# X-LINK-A_V2_0.net
KiCad netlist of a schematic drawn in Altium Designer
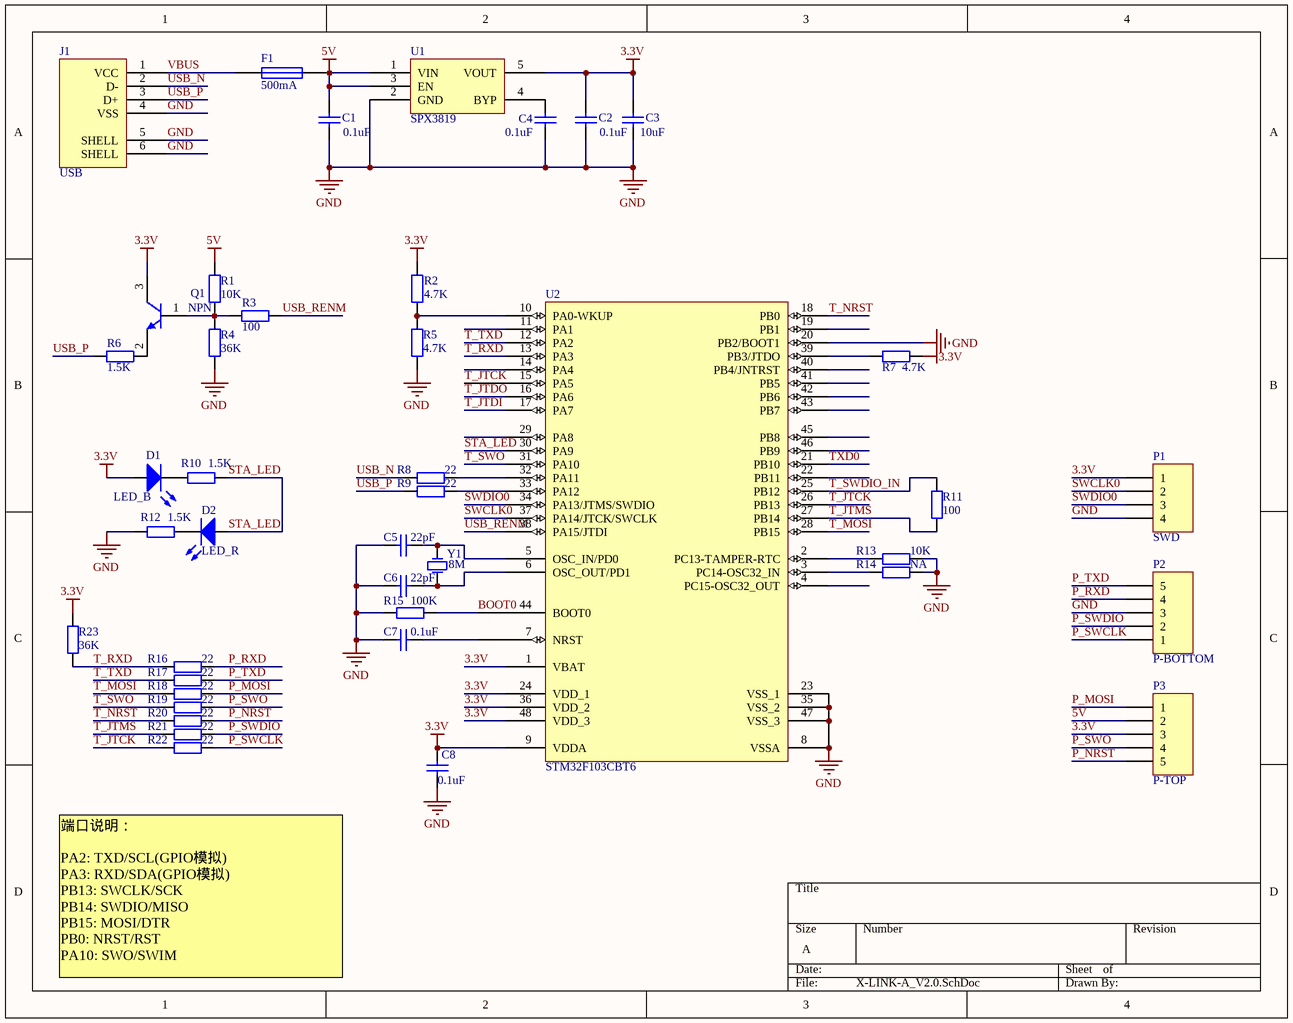
[diagram p0: X-LINK-A_V2.0.SchDoc]

(export (version "E")
  (design (tool "Eeschema 10.0.6"))
  (components
    (comp (ref "C1")
      (value "0.1uF")
      (footprint "C-0603")
      (description "Capacitor")
      (fields (field (name "Comment") "Cap") (field (name "PUBLISHER") "Altium Limited"))
      (libsource (lib "Miscellaneous Devices") (part "Cap"))
    )
    (comp (ref "C2")
      (value "0.1uF")
      (footprint "C-0603")
      (description "Capacitor")
      (fields (field (name "Comment") "Cap") (field (name "PUBLISHER") "Altium Limited"))
      (libsource (lib "Miscellaneous Devices") (part "Cap"))
    )
    (comp (ref "C3")
      (value "10uF")
      (footprint "C-0603")
      (description "Capacitor")
      (fields (field (name "Comment") "Cap") (field (name "PUBLISHER") "Altium Limited"))
      (libsource (lib "Miscellaneous Devices") (part "Cap"))
    )
    (comp (ref "C4")
      (value "0.1uF")
      (footprint "C-0603")
      (description "Capacitor")
      (fields (field (name "Comment") "Cap") (field (name "PUBLISHER") "Altium Limited"))
      (libsource (lib "Miscellaneous Devices") (part "Cap"))
    )
    (comp (ref "C5")
      (value "22pF")
      (footprint "C-0603")
      (fields (field (name "Comment") "Cap"))
      (libsource (lib "WK_PCB") (part "Cap"))
    )
    (comp (ref "C6")
      (value "22pF")
      (footprint "C-0603")
      (fields (field (name "Comment") "Cap"))
      (libsource (lib "WK_PCB") (part "Cap"))
    )
    (comp (ref "C7")
      (value "0.1uF")
      (footprint "C-0603")
      (fields (field (name "Comment") "Cap"))
      (libsource (lib "WK_PCB") (part "Cap"))
    )
    (comp (ref "C8")
      (value "0.1uF")
      (footprint "C-0603")
      (description "Capacitor")
      (fields (field (name "Comment") "Cap") (field (name "PUBLISHER") "Altium Limited"))
      (libsource (lib "Miscellaneous Devices") (part "Cap"))
    )
    (comp (ref "D1")
      (value "LED_B")
      (footprint "SMT_LED_0603")
      (description "Typical RED, GREEN, YELLOW, AMBER GaAs LED")
      (fields (field (name "PUBLISHER") "Altium Limited"))
      (libsource (lib "ST-Link-V2.2") (part "LED2"))
    )
    (comp (ref "D2")
      (value "LED_R")
      (footprint "SMT_LED_0603")
      (description "Typical RED, GREEN, YELLOW, AMBER GaAs LED")
      (fields (field (name "PUBLISHER") "Altium Limited"))
      (libsource (lib "ST-Link-V2.2") (part "LED2"))
    )
    (comp (ref "F1")
      (value "500mA")
      (footprint "0805-1")
      (description "保险丝")
      (fields (field (name "Comment") "Fuse1"))
      (libsource (lib "ST-Link-V2.2") (part "Fuse1"))
    )
    (comp (ref "J1")
      (value "USB")
      (footprint "USB-B")
      (description "USB接口")
      (libsource (lib "HDR_Fszhang") (part "USB"))
    )
    (comp (ref "P1")
      (value "SWD")
      (footprint "SIP4-1.27")
      (description "Header, 4-Pin")
      (fields (field (name "PUBLISHER") "Altium Limited"))
      (libsource (lib "Miscellaneous Connectors") (part "Header 4"))
    )
    (comp (ref "P2")
      (value "P-BOTTOM")
      (footprint "HEADER_5")
      (description "Header, 5-Pin")
      (fields (field (name "PUBLISHER") "Altium Limited"))
      (libsource (lib "") (part "Header 5_1"))
    )
    (comp (ref "P3")
      (value "P-TOP")
      (footprint "HEADER_5")
      (description "Header, 5-Pin")
      (fields (field (name "PUBLISHER") "Altium Limited"))
      (libsource (lib "Miscellaneous Connectors") (part "Header 5"))
    )
    (comp (ref "Q1")
      (value "NPN")
      (footprint "SOT23-3")
      (description "贴片三极管")
      (fields (field (name "PUBLISHER") "Altium Limited"))
      (libsource (lib "Fszhang") (part "NPN1"))
    )
    (comp (ref "R1")
      (value "10K")
      (footprint "0603-1")
      (description "贴片电阻")
      (fields (field (name "Comment") "Res1") (field (name "PUBLISHER") "Altium Limited"))
      (libsource (lib "") (part "Res1_1"))
    )
    (comp (ref "R2")
      (value "4.7K")
      (footprint "0603-1")
      (description "Resistor")
      (fields (field (name "Comment") "Res2") (field (name "PUBLISHER") "Altium Limited"))
      (libsource (lib "Miscellaneous Devices") (part "Res2"))
    )
    (comp (ref "R3")
      (value "100")
      (footprint "0603-1")
      (description "贴片电阻")
      (fields (field (name "Comment") "Res1") (field (name "PUBLISHER") "Altium Limited"))
      (libsource (lib "") (part "Res1_2"))
    )
    (comp (ref "R4")
      (value "36K")
      (footprint "0603-1")
      (description "贴片电阻")
      (fields (field (name "Comment") "Res1") (field (name "PUBLISHER") "Altium Limited"))
      (libsource (lib "") (part "Res1_1"))
    )
    (comp (ref "R5")
      (value "4.7K")
      (footprint "0603-1")
      (description "Resistor")
      (fields (field (name "Comment") "Res2") (field (name "PUBLISHER") "Altium Limited"))
      (libsource (lib "Miscellaneous Devices") (part "Res2"))
    )
    (comp (ref "R6")
      (value "1.5K")
      (footprint "0603-1")
      (description "贴片电阻")
      (fields (field (name "Comment") "Res1") (field (name "PUBLISHER") "Altium Limited"))
      (libsource (lib "Fszhang") (part "Res1"))
    )
    (comp (ref "R7")
      (value "4.7K")
      (footprint "0603-1")
      (description "Resistor")
      (fields (field (name "Comment") "Res2") (field (name "PUBLISHER") "Altium Limited"))
      (libsource (lib "") (part "Res2_1"))
    )
    (comp (ref "R8")
      (value "22")
      (footprint "0603-1")
      (description "Resistor")
      (fields (field (name "Comment") "Res2") (field (name "PUBLISHER") "Altium Limited"))
      (libsource (lib "") (part "Res2_1"))
    )
    (comp (ref "R9")
      (value "22")
      (footprint "0603-1")
      (description "Resistor")
      (fields (field (name "Comment") "Res2") (field (name "PUBLISHER") "Altium Limited"))
      (libsource (lib "") (part "Res2_1"))
    )
    (comp (ref "R10")
      (value "1.5K")
      (footprint "0603-1")
      (description "Resistor")
      (fields (field (name "Comment") "Res2") (field (name "PUBLISHER") "Altium Limited"))
      (libsource (lib "") (part "Res2_1"))
    )
    (comp (ref "R11")
      (value "100")
      (footprint "0603-1")
      (description "Resistor")
      (fields (field (name "Comment") "Res2") (field (name "PUBLISHER") "Altium Limited"))
      (libsource (lib "Miscellaneous Devices") (part "Res2"))
    )
    (comp (ref "R12")
      (value "1.5K")
      (footprint "0603-1")
      (description "Resistor")
      (fields (field (name "Comment") "Res2") (field (name "PUBLISHER") "Altium Limited"))
      (libsource (lib "Miscellaneous Devices") (part "Res2"))
    )
    (comp (ref "R13")
      (value "10K")
      (footprint "0603-1")
      (description "贴片电阻")
      (fields (field (name "Comment") "Res1") (field (name "PUBLISHER") "Altium Limited"))
      (libsource (lib "") (part "Res1_2"))
    )
    (comp (ref "R14")
      (value "NA")
      (footprint "0603-1")
      (description "贴片电阻")
      (fields (field (name "Comment") "Res1") (field (name "PUBLISHER") "Altium Limited"))
      (libsource (lib "") (part "Res1_2"))
    )
    (comp (ref "R15")
      (value "100K")
      (footprint "0603-1")
      (description "Resistor")
      (fields (field (name "Comment") "Res2") (field (name "PUBLISHER") "Altium Limited"))
      (libsource (lib "") (part "Res2_1"))
    )
    (comp (ref "R16")
      (value "22")
      (footprint "0603-1")
      (description "Resistor")
      (fields (field (name "Comment") "Res2") (field (name "PUBLISHER") "Altium Limited"))
      (libsource (lib "") (part "Res2_1"))
    )
    (comp (ref "R17")
      (value "22")
      (footprint "0603-1")
      (description "Resistor")
      (fields (field (name "Comment") "Res2") (field (name "PUBLISHER") "Altium Limited"))
      (libsource (lib "") (part "Res2_1"))
    )
    (comp (ref "R18")
      (value "22")
      (footprint "0603-1")
      (description "Resistor")
      (fields (field (name "Comment") "Res2") (field (name "PUBLISHER") "Altium Limited"))
      (libsource (lib "") (part "Res2_1"))
    )
    (comp (ref "R19")
      (value "22")
      (footprint "0603-1")
      (description "Resistor")
      (fields (field (name "Comment") "Res2") (field (name "PUBLISHER") "Altium Limited"))
      (libsource (lib "") (part "Res2_1"))
    )
    (comp (ref "R20")
      (value "22")
      (footprint "0603-1")
      (description "Resistor")
      (fields (field (name "Comment") "Res2") (field (name "PUBLISHER") "Altium Limited"))
      (libsource (lib "") (part "Res2_1"))
    )
    (comp (ref "R21")
      (value "22")
      (footprint "0603-1")
      (description "Resistor")
      (fields (field (name "Comment") "Res2") (field (name "PUBLISHER") "Altium Limited"))
      (libsource (lib "") (part "Res2_1"))
    )
    (comp (ref "R22")
      (value "22")
      (footprint "0603-1")
      (description "Resistor")
      (fields (field (name "Comment") "Res2") (field (name "PUBLISHER") "Altium Limited"))
      (libsource (lib "") (part "Res2_1"))
    )
    (comp (ref "R23")
      (value "36K")
      (footprint "0603-1")
      (description "贴片电阻")
      (fields (field (name "Comment") "Res1") (field (name "PUBLISHER") "Altium Limited"))
      (libsource (lib "") (part "Res1_1"))
    )
    (comp (ref "U1") (value "SPX3819") (footprint "SOT23-5") (libsource (lib "Schlib1") (part "SPX3819")))
    (comp (ref "U2")
      (value "STM32F103CBT6")
      (footprint "LQFP48_N")
      (description "STM32 ARM-based 32-bit MCU with 64 Kbytes Flash, 48-pin LQFP, Industrial Temperature")
      (fields (field (name "PUBLISHER") "Altium Limited"))
      (libsource (lib "ST Microcontroller 32-Bit STM32") (part "STM32F103C8T6"))
    )
    (comp (ref "Y1")
      (value "8M")
      (footprint "XAL5032 2-Leads")
      (description "Crystal Oscillator")
      (fields
        (field (name "MANUFACTURER") "Generic Components")
        (field (name "PUBLISHER") "Altium Hobart Technology Centre")
      )
      (libsource (lib "*") (part "XTAL"))
    )
  )
  (nets
    (net (code "1") (name "/BOOT0") (class "Default")
      (node (ref "R15") (pin "2") (pinfunction "2_2") (pintype "passive"))
      (node (ref "U2") (pin "44") (pinfunction "BOOT0_44") (pintype "passive"))
    )
    (net (code "2") (name "/P_MOSI") (class "Default")
      (node (ref "P3") (pin "1") (pinfunction "1_1") (pintype "passive"))
      (node (ref "R18") (pin "2") (pinfunction "2_2") (pintype "passive"))
    )
    (net (code "3") (name "/P_NRST") (class "Default")
      (node (ref "P3") (pin "5") (pinfunction "5_5") (pintype "passive"))
      (node (ref "R20") (pin "2") (pinfunction "2_2") (pintype "passive"))
    )
    (net (code "4") (name "/P_RXD") (class "Default")
      (node (ref "P2") (pin "4") (pinfunction "4_4") (pintype "passive"))
      (node (ref "R16") (pin "2") (pinfunction "2_2") (pintype "passive"))
    )
    (net (code "5") (name "/P_SWCLK") (class "Default")
      (node (ref "P2") (pin "1") (pinfunction "1_1") (pintype "passive"))
      (node (ref "R22") (pin "2") (pinfunction "2_2") (pintype "passive"))
    )
    (net (code "6") (name "/P_SWDIO") (class "Default")
      (node (ref "P2") (pin "2") (pinfunction "2_2") (pintype "passive"))
      (node (ref "R21") (pin "2") (pinfunction "2_2") (pintype "passive"))
    )
    (net (code "7") (name "/P_SWO") (class "Default")
      (node (ref "P3") (pin "4") (pinfunction "4_4") (pintype "passive"))
      (node (ref "R19") (pin "2") (pinfunction "2_2") (pintype "passive"))
    )
    (net (code "8") (name "/P_TXD") (class "Default")
      (node (ref "P2") (pin "5") (pinfunction "5_5") (pintype "passive"))
      (node (ref "R17") (pin "2") (pinfunction "2_2") (pintype "passive"))
    )
    (net (code "9") (name "/STA_LED") (class "Default")
      (node (ref "D2") (pin "1") (pinfunction "A_1") (pintype "passive"))
      (node (ref "R10") (pin "2") (pinfunction "2_2") (pintype "passive"))
      (node (ref "U2") (pin "30") (pinfunction "PA9_30") (pintype "bidirectional"))
    )
    (net (code "10") (name "/SWCLK0") (class "Default")
      (node (ref "P1") (pin "2") (pinfunction "2_2") (pintype "passive"))
      (node (ref "U2") (pin "37") (pinfunction "PA14/JTCK/SWCLK_37") (pintype "bidirectional"))
    )
    (net (code "11") (name "/SWDIO0") (class "Default")
      (node (ref "P1") (pin "3") (pinfunction "3_3") (pintype "passive"))
      (node (ref "U2") (pin "34") (pinfunction "PA13/JTMS/SWDIO_34") (pintype "bidirectional"))
    )
    (net (code "12") (name "/TXD0") (class "Default")
      (node (ref "U2") (pin "21") (pinfunction "PB10_21") (pintype "bidirectional"))
    )
    (net (code "13") (name "/T_JTCK") (class "Default")
      (node (ref "R22") (pin "1") (pinfunction "1_1") (pintype "passive"))
      (node (ref "U2") (pin "15") (pinfunction "PA5_15") (pintype "bidirectional"))
      (node (ref "U2") (pin "26") (pinfunction "PB13_26") (pintype "bidirectional"))
    )
    (net (code "14") (name "/T_JTDI") (class "Default")
      (node (ref "U2") (pin "17") (pinfunction "PA7_17") (pintype "bidirectional"))
    )
    (net (code "15") (name "/T_JTDO") (class "Default")
      (node (ref "U2") (pin "16") (pinfunction "PA6_16") (pintype "bidirectional"))
    )
    (net (code "16") (name "/T_JTMS") (class "Default")
      (node (ref "R11") (pin "1") (pinfunction "1_1") (pintype "passive"))
      (node (ref "R21") (pin "1") (pinfunction "1_1") (pintype "passive"))
      (node (ref "U2") (pin "27") (pinfunction "PB14_27") (pintype "bidirectional"))
    )
    (net (code "17") (name "/T_MOSI") (class "Default")
      (node (ref "R18") (pin "1") (pinfunction "1_1") (pintype "passive"))
      (node (ref "U2") (pin "28") (pinfunction "PB15_28") (pintype "bidirectional"))
    )
    (net (code "18") (name "/T_NRST") (class "Default")
      (node (ref "R20") (pin "1") (pinfunction "1_1") (pintype "passive"))
      (node (ref "U2") (pin "18") (pinfunction "PB0_18") (pintype "bidirectional"))
    )
    (net (code "19") (name "/T_RXD") (class "Default")
      (node (ref "R16") (pin "1") (pinfunction "1_1") (pintype "passive"))
      (node (ref "R23") (pin "2") (pinfunction "2_2") (pintype "passive"))
      (node (ref "U2") (pin "13") (pinfunction "PA3_13") (pintype "bidirectional"))
    )
    (net (code "20") (name "/T_SWDIO_IN") (class "Default")
      (node (ref "R11") (pin "2") (pinfunction "2_2") (pintype "passive"))
      (node (ref "U2") (pin "25") (pinfunction "PB12_25") (pintype "bidirectional"))
    )
    (net (code "21") (name "/T_SWO") (class "Default")
      (node (ref "R19") (pin "1") (pinfunction "1_1") (pintype "passive"))
      (node (ref "U2") (pin "31") (pinfunction "PA10_31") (pintype "bidirectional"))
    )
    (net (code "22") (name "/T_TXD") (class "Default")
      (node (ref "R17") (pin "1") (pinfunction "1_1") (pintype "passive"))
      (node (ref "U2") (pin "12") (pinfunction "PA2_12") (pintype "bidirectional"))
    )
    (net (code "23") (name "/USB_N") (class "Default")
      (node (ref "J1") (pin "2") (pinfunction "D-_2") (pintype "passive"))
      (node (ref "R8") (pin "1") (pinfunction "1_1") (pintype "passive"))
    )
    (net (code "24") (name "/USB_P") (class "Default")
      (node (ref "J1") (pin "3") (pinfunction "D+_3") (pintype "passive"))
      (node (ref "R6") (pin "2") (pinfunction "2_2") (pintype "passive"))
      (node (ref "R9") (pin "1") (pinfunction "1_1") (pintype "passive"))
    )
    (net (code "25") (name "/USB_RENM") (class "Default")
      (node (ref "R3") (pin "2") (pinfunction "2_2") (pintype "passive"))
      (node (ref "U2") (pin "38") (pinfunction "PA15/JTDI_38") (pintype "bidirectional"))
    )
    (net (code "26") (name "/VBUS") (class "Default")
      (node (ref "F1") (pin "1") (pinfunction "1_1") (pintype "passive"))
      (node (ref "J1") (pin "1") (pinfunction "VCC_1") (pintype "passive"))
    )
    (net (code "27") (name "3.3V") (class "Default")
      (node (ref "C2") (pin "2") (pinfunction "2_2") (pintype "passive"))
      (node (ref "C3") (pin "2") (pinfunction "2_2") (pintype "passive"))
      (node (ref "C8") (pin "2") (pinfunction "2_2") (pintype "passive"))
      (node (ref "D1") (pin "1") (pinfunction "A_1") (pintype "passive"))
      (node (ref "P1") (pin "1") (pinfunction "1_1") (pintype "passive"))
      (node (ref "P3") (pin "3") (pinfunction "3_3") (pintype "passive"))
      (node (ref "Q1") (pin "3") (pinfunction "C_3") (pintype "passive"))
      (node (ref "R2") (pin "2") (pinfunction "2_2") (pintype "passive"))
      (node (ref "R23") (pin "1") (pinfunction "1_1") (pintype "passive"))
      (node (ref "R7") (pin "2") (pinfunction "2_2") (pintype "passive"))
      (node (ref "U1") (pin "5") (pinfunction "VOUT_5") (pintype "passive"))
      (node (ref "U2") (pin "1") (pinfunction "VBAT_1") (pintype "power_in"))
      (node (ref "U2") (pin "24") (pinfunction "VDD_1_24") (pintype "power_in"))
      (node (ref "U2") (pin "36") (pinfunction "VDD_2_36") (pintype "power_in"))
      (node (ref "U2") (pin "48") (pinfunction "VDD_3_48") (pintype "power_in"))
      (node (ref "U2") (pin "9") (pinfunction "VDDA_9") (pintype "power_in"))
    )
    (net (code "28") (name "5V") (class "Default")
      (node (ref "C1") (pin "2") (pinfunction "2_2") (pintype "passive"))
      (node (ref "F1") (pin "2") (pinfunction "2_2") (pintype "passive"))
      (node (ref "P3") (pin "2") (pinfunction "2_2") (pintype "passive"))
      (node (ref "R1") (pin "1") (pinfunction "1_1") (pintype "passive"))
      (node (ref "U1") (pin "1") (pinfunction "VIN_1") (pintype "passive"))
      (node (ref "U1") (pin "3") (pinfunction "EN_3") (pintype "passive"))
    )
    (net (code "29") (name "GND") (class "Default")
      (node (ref "C1") (pin "1") (pinfunction "1_1") (pintype "passive"))
      (node (ref "C2") (pin "1") (pinfunction "1_1") (pintype "passive"))
      (node (ref "C3") (pin "1") (pinfunction "1_1") (pintype "passive"))
      (node (ref "C4") (pin "1") (pinfunction "1_1") (pintype "passive"))
      (node (ref "C5") (pin "1") (pinfunction "1_1") (pintype "passive"))
      (node (ref "C6") (pin "1") (pinfunction "1_1") (pintype "passive"))
      (node (ref "C7") (pin "1") (pinfunction "1_1") (pintype "passive"))
      (node (ref "C8") (pin "1") (pinfunction "1_1") (pintype "passive"))
      (node (ref "J1") (pin "4") (pinfunction "VSS_4") (pintype "passive"))
      (node (ref "J1") (pin "5") (pinfunction "SHELL_5") (pintype "passive"))
      (node (ref "J1") (pin "6") (pinfunction "SHELL_6") (pintype "passive"))
      (node (ref "P1") (pin "4") (pinfunction "4_4") (pintype "passive"))
      (node (ref "P2") (pin "3") (pinfunction "3_3") (pintype "passive"))
      (node (ref "R12") (pin "1") (pinfunction "1_1") (pintype "passive"))
      (node (ref "R13") (pin "2") (pinfunction "2_2") (pintype "passive"))
      (node (ref "R14") (pin "2") (pinfunction "2_2") (pintype "passive"))
      (node (ref "R15") (pin "1") (pinfunction "1_1") (pintype "passive"))
      (node (ref "R4") (pin "2") (pinfunction "2_2") (pintype "passive"))
      (node (ref "R5") (pin "1") (pinfunction "1_1") (pintype "passive"))
      (node (ref "U1") (pin "2") (pinfunction "GND_2") (pintype "passive"))
      (node (ref "U2") (pin "20") (pinfunction "PB2/BOOT1_20") (pintype "bidirectional"))
      (node (ref "U2") (pin "23") (pinfunction "VSS_1_23") (pintype "power_in"))
      (node (ref "U2") (pin "35") (pinfunction "VSS_2_35") (pintype "power_in"))
      (node (ref "U2") (pin "47") (pinfunction "VSS_3_47") (pintype "power_in"))
      (node (ref "U2") (pin "8") (pinfunction "VSSA_8") (pintype "power_in"))
    )
    (net (code "30") (name "Net-(D1-K)") (class "Default")
      (node (ref "D1") (pin "2") (pinfunction "K_2") (pintype "passive"))
      (node (ref "R10") (pin "1") (pinfunction "1_1") (pintype "passive"))
    )
    (net (code "31") (name "Net-(D2-K)") (class "Default")
      (node (ref "D2") (pin "2") (pinfunction "K_2") (pintype "passive"))
      (node (ref "R12") (pin "2") (pinfunction "2_2") (pintype "passive"))
    )
    (net (code "32") (name "Net-(Q1-B)") (class "Default")
      (node (ref "Q1") (pin "1") (pinfunction "B_1") (pintype "passive"))
      (node (ref "R1") (pin "2") (pinfunction "2_2") (pintype "passive"))
      (node (ref "R3") (pin "1") (pinfunction "1_1") (pintype "passive"))
      (node (ref "R4") (pin "1") (pinfunction "1_1") (pintype "passive"))
    )
    (net (code "33") (name "Net-(Q1-E)") (class "Default")
      (node (ref "Q1") (pin "2") (pinfunction "E_2") (pintype "passive"))
      (node (ref "R6") (pin "1") (pinfunction "1_1") (pintype "passive"))
    )
    (net (code "34") (name "Net-(U1-BYP)") (class "Default")
      (node (ref "C4") (pin "2") (pinfunction "2_2") (pintype "passive"))
      (node (ref "U1") (pin "4") (pinfunction "BYP_4") (pintype "passive"))
    )
    (net (code "35") (name "Net-(U2-NRST)") (class "Default")
      (node (ref "C7") (pin "2") (pinfunction "2_2") (pintype "passive"))
      (node (ref "U2") (pin "7") (pinfunction "NRST_7") (pintype "bidirectional"))
    )
    (net (code "36") (name "Net-(U2-OSC_IN{slash}PD0)") (class "Default")
      (node (ref "C5") (pin "2") (pinfunction "2_2") (pintype "passive"))
      (node (ref "U2") (pin "5") (pinfunction "OSC_IN/PD0_5") (pintype "passive"))
      (node (ref "Y1") (pin "1") (pinfunction "OSC1_1") (pintype "passive"))
    )
    (net (code "37") (name "Net-(U2-OSC_OUT{slash}PD1)") (class "Default")
      (node (ref "C6") (pin "2") (pinfunction "2_2") (pintype "passive"))
      (node (ref "U2") (pin "6") (pinfunction "OSC_OUT/PD1_6") (pintype "passive"))
      (node (ref "Y1") (pin "2") (pinfunction "OSC2_2") (pintype "passive"))
    )
    (net (code "38") (name "Net-(U2-PA0-WKUP)") (class "Default")
      (node (ref "R2") (pin "1") (pinfunction "1_1") (pintype "passive"))
      (node (ref "R5") (pin "2") (pinfunction "2_2") (pintype "passive"))
      (node (ref "U2") (pin "10") (pinfunction "PA0-WKUP_10") (pintype "bidirectional"))
    )
    (net (code "39") (name "Net-(U2-PA11)") (class "Default")
      (node (ref "R8") (pin "2") (pinfunction "2_2") (pintype "passive"))
      (node (ref "U2") (pin "32") (pinfunction "PA11_32") (pintype "bidirectional"))
    )
    (net (code "40") (name "Net-(U2-PA12)") (class "Default")
      (node (ref "R9") (pin "2") (pinfunction "2_2") (pintype "passive"))
      (node (ref "U2") (pin "33") (pinfunction "PA12_33") (pintype "bidirectional"))
    )
    (net (code "41") (name "Net-(U2-PB3{slash}JTDO)") (class "Default")
      (node (ref "R7") (pin "1") (pinfunction "1_1") (pintype "passive"))
      (node (ref "U2") (pin "39") (pinfunction "PB3/JTDO_39") (pintype "bidirectional"))
    )
    (net (code "42") (name "Net-(U2-PC13-TAMPER-RTC)") (class "Default")
      (node (ref "R13") (pin "1") (pinfunction "1_1") (pintype "passive"))
      (node (ref "U2") (pin "2") (pinfunction "PC13-TAMPER-RTC_2") (pintype "bidirectional"))
    )
    (net (code "43") (name "Net-(U2-PC14-OSC32_IN)") (class "Default")
      (node (ref "R14") (pin "1") (pinfunction "1_1") (pintype "passive"))
      (node (ref "U2") (pin "3") (pinfunction "PC14-OSC32_IN_3") (pintype "bidirectional"))
    )
    (net (code "44") (name "unconnected-(U2-PA1-Pad11)") (class "Default")
      (node (ref "U2") (pin "11") (pinfunction "PA1_11") (pintype "bidirectional"))
    )
    (net (code "45") (name "unconnected-(U2-PA4-Pad14)") (class "Default")
      (node (ref "U2") (pin "14") (pinfunction "PA4_14") (pintype "bidirectional"))
    )
    (net (code "46") (name "unconnected-(U2-PA8-Pad29)") (class "Default")
      (node (ref "U2") (pin "29") (pinfunction "PA8_29") (pintype "bidirectional"))
    )
    (net (code "47") (name "unconnected-(U2-PB1-Pad19)") (class "Default")
      (node (ref "U2") (pin "19") (pinfunction "PB1_19") (pintype "bidirectional"))
    )
    (net (code "48") (name "unconnected-(U2-PB4{slash}JNTRST-Pad40)") (class "Default")
      (node (ref "U2") (pin "40") (pinfunction "PB4/JNTRST_40") (pintype "bidirectional"))
    )
    (net (code "49") (name "unconnected-(U2-PB5-Pad41)") (class "Default")
      (node (ref "U2") (pin "41") (pinfunction "PB5_41") (pintype "bidirectional"))
    )
    (net (code "50") (name "unconnected-(U2-PB6-Pad42)") (class "Default")
      (node (ref "U2") (pin "42") (pinfunction "PB6_42") (pintype "bidirectional"))
    )
    (net (code "51") (name "unconnected-(U2-PB7-Pad43)") (class "Default")
      (node (ref "U2") (pin "43") (pinfunction "PB7_43") (pintype "bidirectional"))
    )
    (net (code "52") (name "unconnected-(U2-PB8-Pad45)") (class "Default")
      (node (ref "U2") (pin "45") (pinfunction "PB8_45") (pintype "bidirectional"))
    )
    (net (code "53") (name "unconnected-(U2-PB9-Pad46)") (class "Default")
      (node (ref "U2") (pin "46") (pinfunction "PB9_46") (pintype "bidirectional"))
    )
    (net (code "54") (name "unconnected-(U2-PB11-Pad22)") (class "Default")
      (node (ref "U2") (pin "22") (pinfunction "PB11_22") (pintype "bidirectional"))
    )
    (net (code "55") (name "unconnected-(U2-PC15-OSC32_OUT-Pad4)") (class "Default")
      (node (ref "U2") (pin "4") (pinfunction "PC15-OSC32_OUT_4") (pintype "bidirectional"))
    )
  )
)
